# pt100.net
KiCad netlist of a schematic drawn in Altium Designer
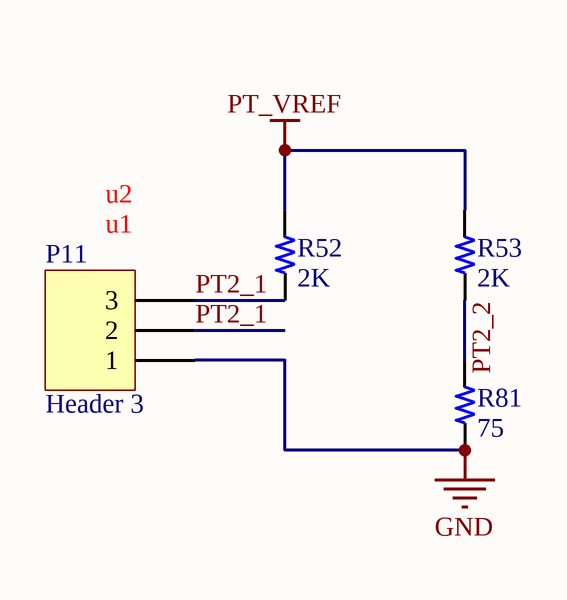
[diagram p0: pt100.SchDoc]

(export (version "E")
  (design (tool "Eeschema 10.0.6"))
  (components
    (comp (ref "P11")
      (value "Header 3")
      (footprint "KF7.62-3P")
      (description "Header, 3-Pin")
      (fields (field (name "PUBLISHER") "Altium Limited"))
      (libsource (lib "Miscellaneous Connectors") (part "Header 3"))
    )
    (comp (ref "R52") (value "2K") (footprint "0603R") (libsource (lib "JRJ_1") (part "R")))
    (comp (ref "R53") (value "2K") (footprint "0603R") (libsource (lib "JRJ_1") (part "R")))
    (comp (ref "R81") (value "75") (footprint "0603R") (libsource (lib "JRJ_1") (part "R")))
  )
  (nets
    (net (code "1") (name "/PT2_1") (class "Default")
      (node (ref "P11") (pin "2") (pinfunction "2_2") (pintype "passive"))
      (node (ref "P11") (pin "3") (pinfunction "3_3") (pintype "passive"))
      (node (ref "R52") (pin "1") (pintype "passive"))
    )
    (net (code "2") (name "/PT2_2") (class "Default")
      (node (ref "R53") (pin "1") (pintype "passive"))
      (node (ref "R81") (pin "2") (pintype "passive"))
    )
    (net (code "3") (name "GND") (class "Default")
      (node (ref "P11") (pin "1") (pinfunction "1_1") (pintype "passive"))
      (node (ref "R81") (pin "1") (pintype "passive"))
    )
    (net (code "4") (name "PT_VREF") (class "Default")
      (node (ref "R52") (pin "2") (pintype "passive"))
      (node (ref "R53") (pin "2") (pintype "passive"))
    )
  )
)
